# SCH_YZ_FFC_to_Microfit_2022-07-01.net
KiCad netlist of a schematic drawn in EasyEDA
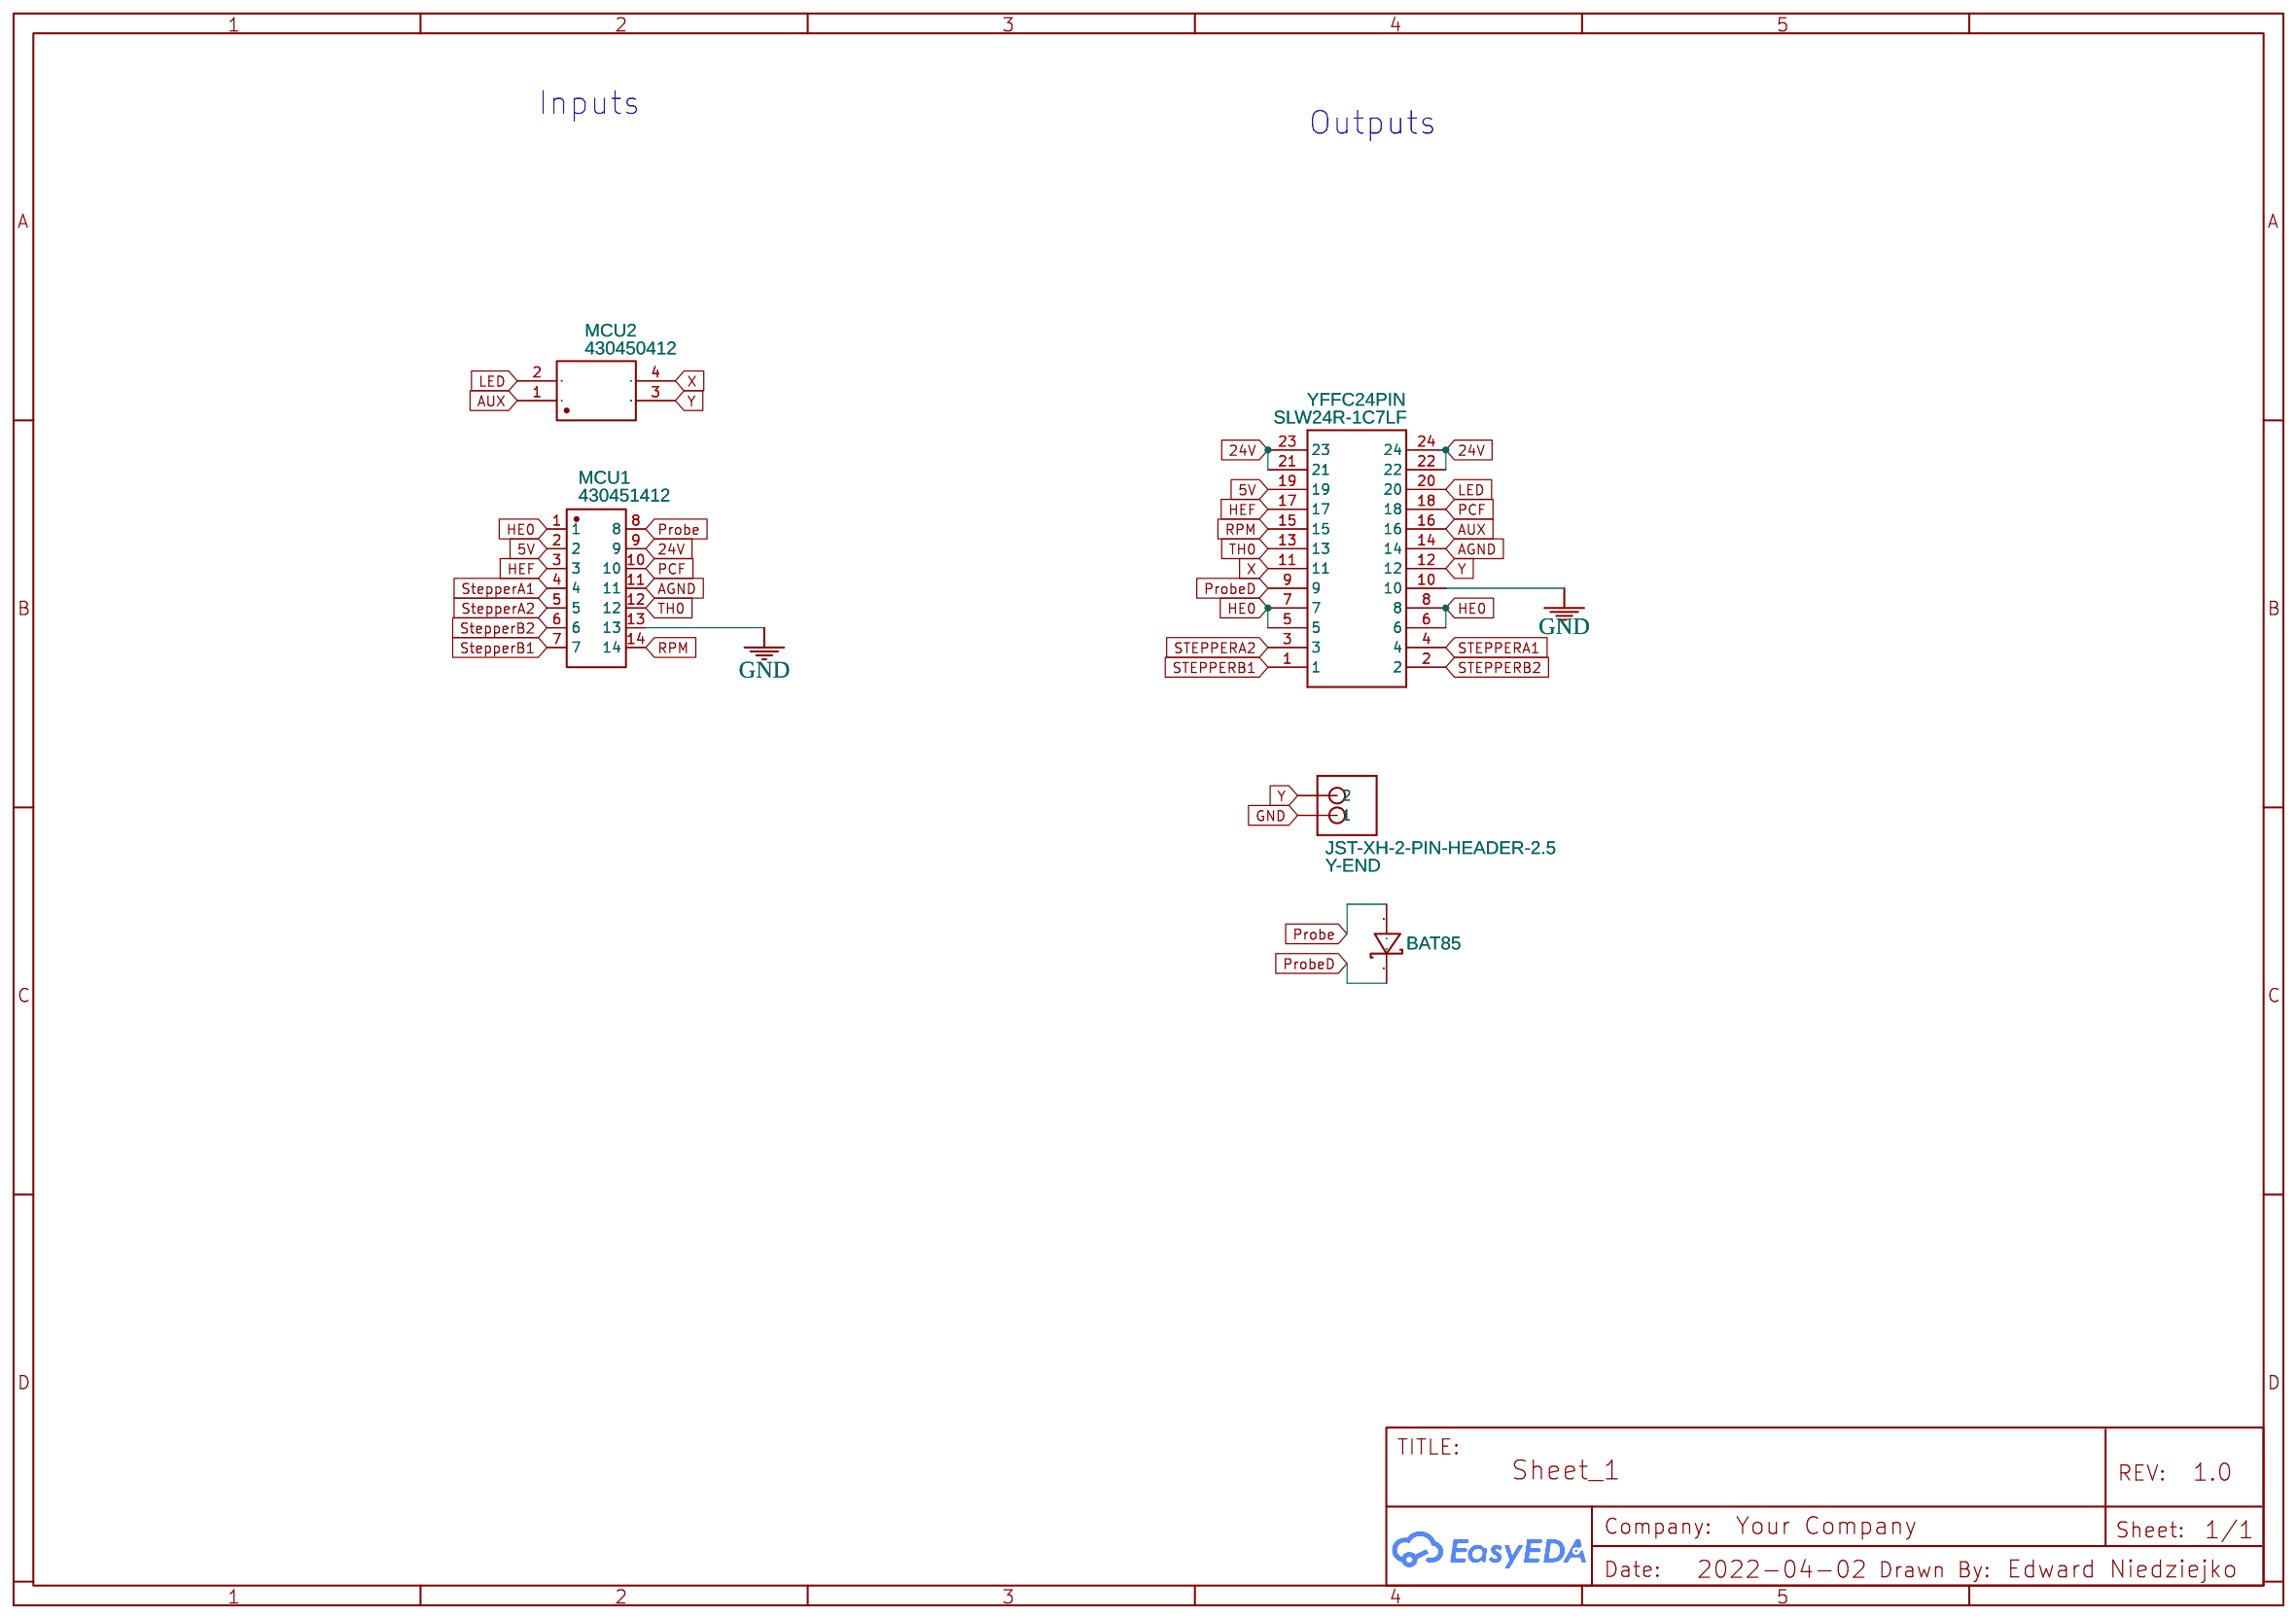
[diagram p0: schematic sheet]

(export (version "E")
  (design (tool "Eeschema 10.0.6"))
  (components
    (comp (ref "BAT85")
      (value "BAT85")
      (fields (field (name "BOM_Manufacturer Part") "BAT85,133") (field (name "BOM_Supplier Part") "C134301"))
      (libsource (lib "") (part "BAT85,133"))
    )
    (comp (ref "MCU1")
      (value "430451412")
      (fields (field (name "BOM_Supplier Part") "C293738"))
      (libsource (lib "") (part "430451412"))
    )
    (comp (ref "MCU2")
      (value "430450412")
      (fields (field (name "BOM_Supplier Part") "C277721"))
      (libsource (lib "") (part "430450412"))
    )
    (comp (ref "Y-END")
      (value "JST-XH-2-PIN-HEADER-2.5")
      (libsource (lib "") (part "JST-XH-2-PIN-HEADER-2.5"))
    )
    (comp (ref "YFFC24PIN") (value "SLW24R-1C7LF") (libsource (lib "") (part "SLW24R-1C7LF")))
  )
  (nets
    (net (code "1") (name "5V") (class "Default")
      (node (ref "MCU1") (pin "2") (pinfunction "2_2") (pintype "unspecified"))
      (node (ref "YFFC24PIN") (pin "19") (pinfunction "19_19") (pintype "bidirectional"))
    )
    (net (code "2") (name "24V") (class "Default")
      (node (ref "MCU1") (pin "9") (pinfunction "9_9") (pintype "unspecified"))
      (node (ref "YFFC24PIN") (pin "21") (pinfunction "21_21") (pintype "bidirectional"))
      (node (ref "YFFC24PIN") (pin "22") (pinfunction "22_22") (pintype "bidirectional"))
      (node (ref "YFFC24PIN") (pin "23") (pinfunction "23_23") (pintype "bidirectional"))
      (node (ref "YFFC24PIN") (pin "24") (pinfunction "24_24") (pintype "bidirectional"))
    )
    (net (code "3") (name "AGND") (class "Default")
      (node (ref "MCU1") (pin "11") (pinfunction "11_11") (pintype "unspecified"))
      (node (ref "YFFC24PIN") (pin "14") (pinfunction "14_14") (pintype "bidirectional"))
    )
    (net (code "4") (name "AUX") (class "Default")
      (node (ref "MCU2") (pin "1") (pinfunction "1_1") (pintype "unspecified"))
      (node (ref "YFFC24PIN") (pin "16") (pinfunction "16_16") (pintype "bidirectional"))
    )
    (net (code "5") (name "GND") (class "Default")
      (node (ref "MCU1") (pin "13") (pinfunction "13_13") (pintype "unspecified"))
      (node (ref "Y-END") (pin "1") (pinfunction "1_1") (pintype "unspecified"))
      (node (ref "YFFC24PIN") (pin "10") (pinfunction "10_10") (pintype "bidirectional"))
    )
    (net (code "6") (name "HE0") (class "Default")
      (node (ref "MCU1") (pin "1") (pinfunction "1_1") (pintype "unspecified"))
      (node (ref "YFFC24PIN") (pin "5") (pinfunction "5_5") (pintype "bidirectional"))
      (node (ref "YFFC24PIN") (pin "6") (pinfunction "6_6") (pintype "bidirectional"))
      (node (ref "YFFC24PIN") (pin "7") (pinfunction "7_7") (pintype "bidirectional"))
      (node (ref "YFFC24PIN") (pin "8") (pinfunction "8_8") (pintype "bidirectional"))
    )
    (net (code "7") (name "HEF") (class "Default")
      (node (ref "MCU1") (pin "3") (pinfunction "3_3") (pintype "unspecified"))
      (node (ref "YFFC24PIN") (pin "17") (pinfunction "17_17") (pintype "bidirectional"))
    )
    (net (code "8") (name "LED") (class "Default")
      (node (ref "MCU2") (pin "2") (pinfunction "2_2") (pintype "unspecified"))
      (node (ref "YFFC24PIN") (pin "20") (pinfunction "20_20") (pintype "bidirectional"))
    )
    (net (code "9") (name "PCF") (class "Default")
      (node (ref "MCU1") (pin "10") (pinfunction "10_10") (pintype "unspecified"))
      (node (ref "YFFC24PIN") (pin "18") (pinfunction "18_18") (pintype "bidirectional"))
    )
    (net (code "10") (name "Probe") (class "Default")
      (node (ref "BAT85") (pin "2") (pinfunction "A_2") (pintype "unspecified"))
      (node (ref "MCU1") (pin "8") (pinfunction "8_8") (pintype "unspecified"))
    )
    (net (code "11") (name "ProbeD") (class "Default")
      (node (ref "BAT85") (pin "1") (pinfunction "K_1") (pintype "unspecified"))
      (node (ref "YFFC24PIN") (pin "9") (pinfunction "9_9") (pintype "bidirectional"))
    )
    (net (code "12") (name "RPM") (class "Default")
      (node (ref "MCU1") (pin "14") (pinfunction "14_14") (pintype "unspecified"))
      (node (ref "YFFC24PIN") (pin "15") (pinfunction "15_15") (pintype "bidirectional"))
    )
    (net (code "13") (name "STEPPERA1") (class "Default")
      (node (ref "YFFC24PIN") (pin "4") (pinfunction "4_4") (pintype "bidirectional"))
    )
    (net (code "14") (name "STEPPERA2") (class "Default")
      (node (ref "YFFC24PIN") (pin "3") (pinfunction "3_3") (pintype "bidirectional"))
    )
    (net (code "15") (name "STEPPERB1") (class "Default")
      (node (ref "YFFC24PIN") (pin "1") (pinfunction "1_1") (pintype "bidirectional"))
    )
    (net (code "16") (name "STEPPERB2") (class "Default")
      (node (ref "YFFC24PIN") (pin "2") (pinfunction "2_2") (pintype "bidirectional"))
    )
    (net (code "17") (name "StepperA1") (class "Default")
      (node (ref "MCU1") (pin "4") (pinfunction "4_4") (pintype "unspecified"))
    )
    (net (code "18") (name "StepperA2") (class "Default")
      (node (ref "MCU1") (pin "5") (pinfunction "5_5") (pintype "unspecified"))
    )
    (net (code "19") (name "StepperB1") (class "Default")
      (node (ref "MCU1") (pin "7") (pinfunction "7_7") (pintype "unspecified"))
    )
    (net (code "20") (name "StepperB2") (class "Default")
      (node (ref "MCU1") (pin "6") (pinfunction "6_6") (pintype "unspecified"))
    )
    (net (code "21") (name "TH0") (class "Default")
      (node (ref "MCU1") (pin "12") (pinfunction "12_12") (pintype "unspecified"))
      (node (ref "YFFC24PIN") (pin "13") (pinfunction "13_13") (pintype "bidirectional"))
    )
    (net (code "22") (name "X") (class "Default")
      (node (ref "MCU2") (pin "4") (pinfunction "4_4") (pintype "unspecified"))
      (node (ref "YFFC24PIN") (pin "11") (pinfunction "11_11") (pintype "bidirectional"))
    )
    (net (code "23") (name "Y") (class "Default")
      (node (ref "MCU2") (pin "3") (pinfunction "3_3") (pintype "unspecified"))
      (node (ref "Y-END") (pin "2") (pinfunction "2_2") (pintype "unspecified"))
      (node (ref "YFFC24PIN") (pin "12") (pinfunction "12_12") (pintype "bidirectional"))
    )
  )
)
